# 4180_Board_rev1.net
KiCad netlist of a schematic drawn in EAGLE
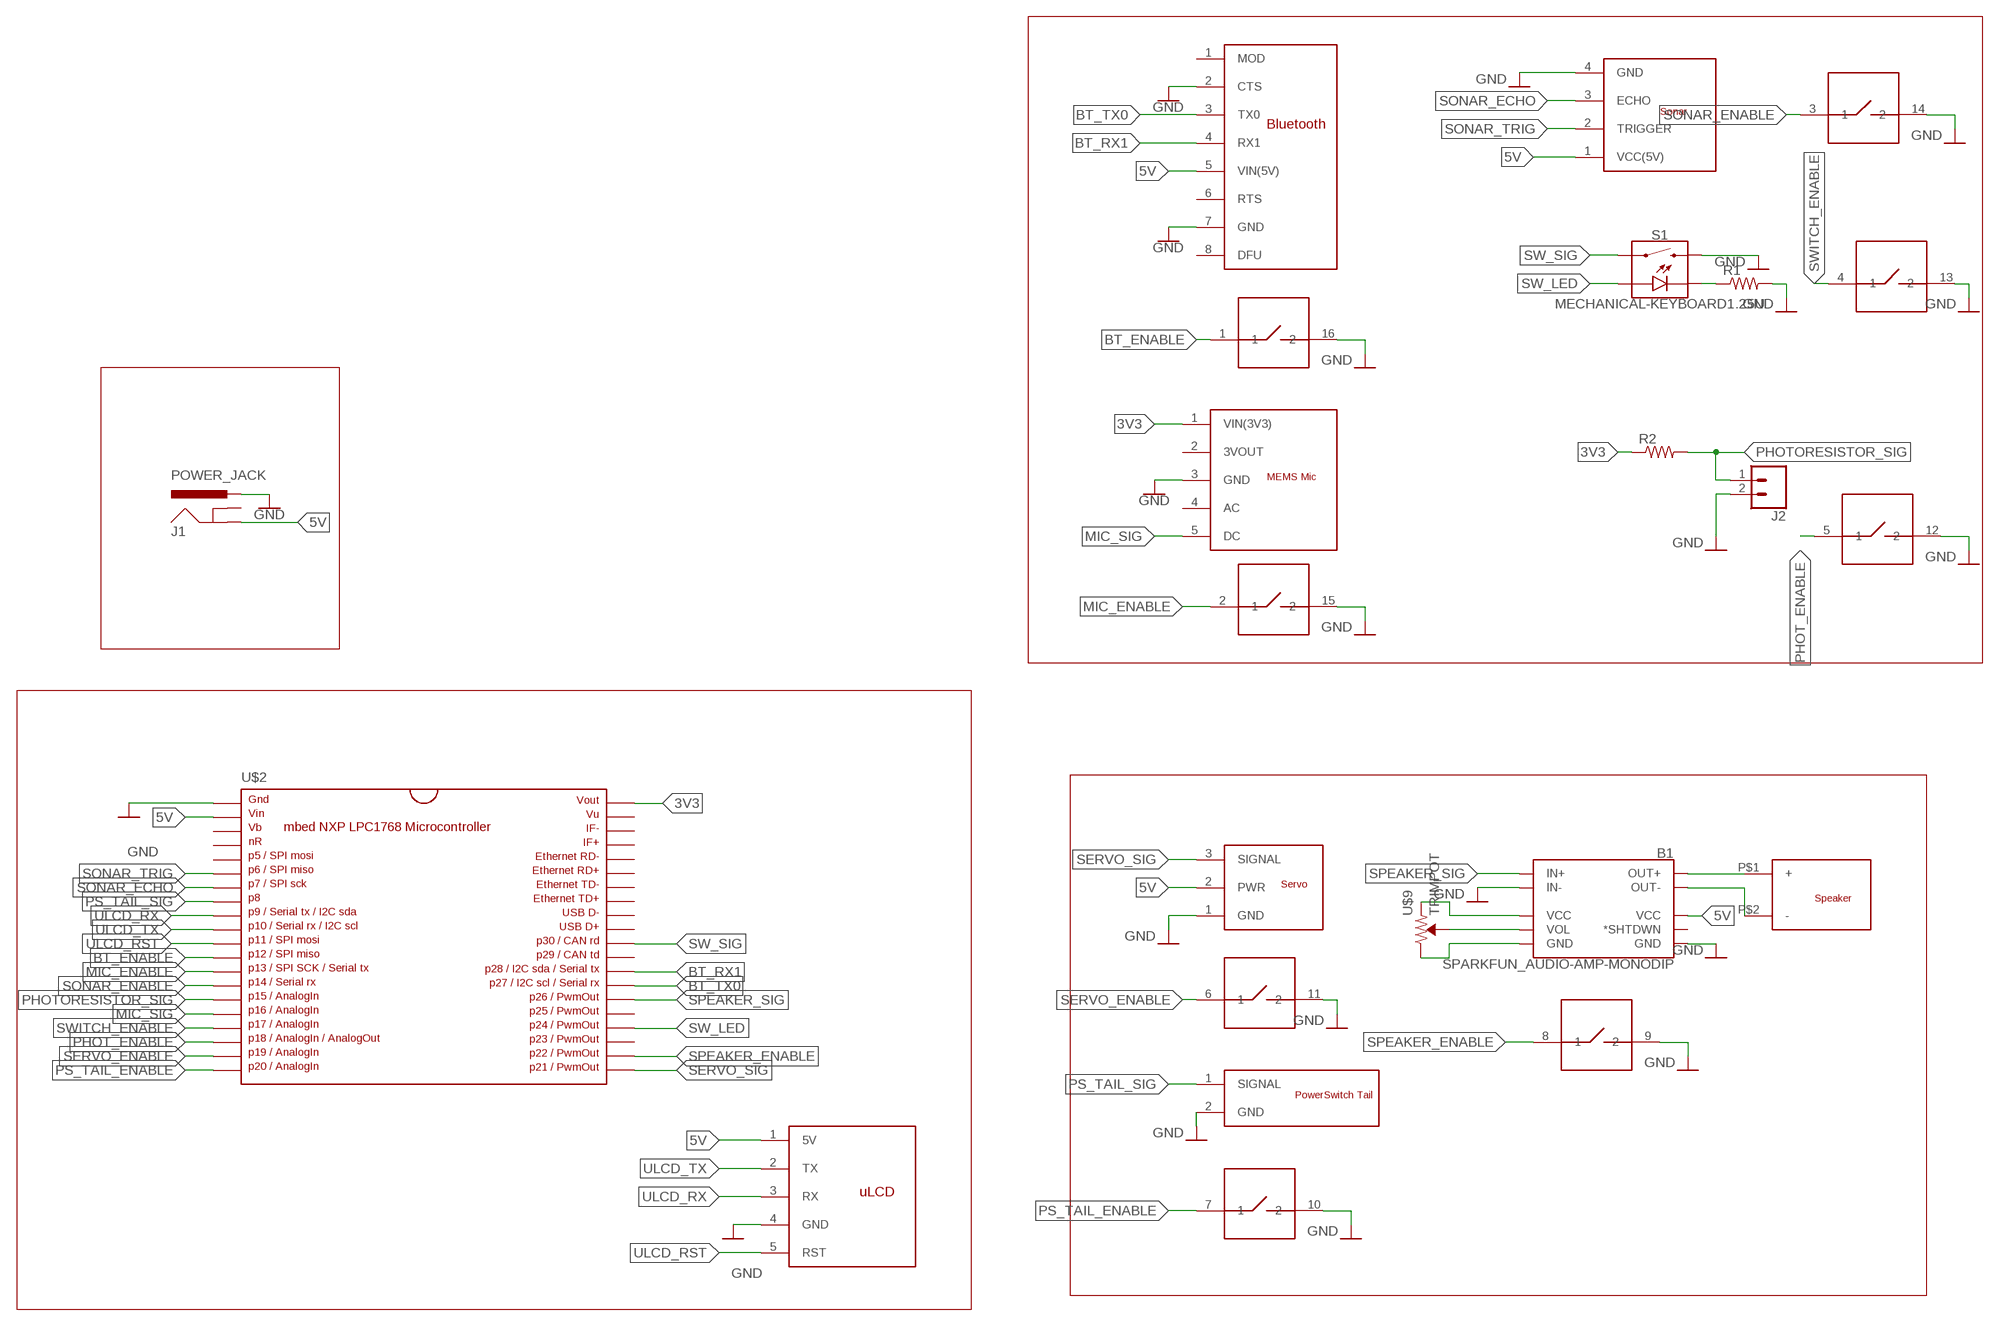
[diagram p0: schematic, sheet 1]

(export (version "E")
  (design (tool "Eeschema 10.0.6"))
  (components
    (comp (ref "B1")
      (value "SPARKFUN_AUDIO-AMP-MONODIP")
      (footprint "eagle-import:AUDIO-AMP-MONO")
      (libsource (lib "eagle-import") (part "SPARKFUN_AUDIO-AMP-MONODIP"))
    )
    (comp (ref "J1")
      (value "POWER_JACK")
      (footprint "eagle-import:POWER_JACK_PTH")
      (libsource (lib "eagle-import") (part "POWER_JACK"))
    )
    (comp (ref "J2")
      (value "CONN_02")
      (footprint "eagle-import:1X02")
      (libsource (lib "eagle-import") (part "CONN_02"))
    )
    (comp (ref "R1")
      (value "ADAFRUIT_R-US_0309/12")
      (footprint "eagle-import:ADAFRUIT_0309_12")
      (libsource (lib "eagle-import") (part "ADAFRUIT_R-US_0309/12"))
    )
    (comp (ref "R2")
      (value "ADAFRUIT_R-US_0309/12")
      (footprint "eagle-import:ADAFRUIT_0309_12")
      (libsource (lib "eagle-import") (part "ADAFRUIT_R-US_0309/12"))
    )
    (comp (ref "S1")
      (value "MECHANICAL-KEYBOARD1.25U")
      (footprint "eagle-import:CHERRY-MX-LED-1.25U")
      (libsource (lib "eagle-import") (part "MECHANICAL-KEYBOARD1.25U"))
    )
    (comp (ref "U$1")
      (value "BLUETOOTH")
      (footprint "eagle-import:1X08")
      (libsource (lib "eagle-import") (part "BLUETOOTH"))
    )
    (comp (ref "U$2")
      (value "MBED1768")
      (footprint "eagle-import:DIL40_0.9")
      (libsource (lib "eagle-import") (part "MBED_NXP_LPC1768"))
    )
    (comp (ref "U$3")
      (value "MEMS_MIC")
      (footprint "eagle-import:1X05")
      (libsource (lib "eagle-import") (part "MEMS_MIC"))
    )
    (comp (ref "U$4")
      (value "POWERSWITCHTAIL")
      (footprint "eagle-import:1X02")
      (libsource (lib "eagle-import") (part "POWERSWITCHTAIL"))
    )
    (comp (ref "U$5")
      (value "SERVO")
      (footprint "eagle-import:1X03")
      (libsource (lib "eagle-import") (part "SERVO"))
    )
    (comp (ref "U$6")
      (value "SONAR")
      (footprint "eagle-import:1X04")
      (libsource (lib "eagle-import") (part "SONAR"))
    )
    (comp (ref "U$7")
      (value "SPEAKER")
      (footprint "eagle-import:SPEAKER")
      (libsource (lib "eagle-import") (part "SPEAKER"))
    )
    (comp (ref "U$8")
      (value "ULCD")
      (footprint "eagle-import:1X05")
      (libsource (lib "eagle-import") (part "ULCD"))
    )
    (comp (ref "U$9")
      (value "TRIMPOT")
      (footprint "eagle-import:TRIMPOT")
      (libsource (lib "eagle-import") (part "TRIMPOT"))
    )
    (comp (ref "U$10")
      (value "DIP_SWITCH_8")
      (footprint "eagle-import:DIP16")
      (libsource (lib "eagle-import") (part "DIP_SWITCH_8"))
    )
  )
  (nets
    (net (code "1") (name "3V3") (class "Default")
      (node (ref "R2") (pin "1") (pinfunction "1_1") (pintype "passive"))
      (node (ref "U$2") (pin "40") (pinfunction "P$40_40") (pintype "bidirectional"))
      (node (ref "U$3") (pin "1") (pinfunction "VIN(3V3)_1") (pintype "bidirectional"))
    )
    (net (code "2") (name "5V") (class "Default")
      (node (ref "B1") (pin "PWR+") (pinfunction "VCC_PWR+") (pintype "bidirectional"))
      (node (ref "J1") (pin "PWR") (pinfunction "GND_PWR") (pintype "bidirectional"))
      (node (ref "U$1") (pin "5") (pinfunction "VIN(5V)_5") (pintype "bidirectional"))
      (node (ref "U$2") (pin "2") (pinfunction "P$2_2") (pintype "bidirectional"))
      (node (ref "U$5") (pin "2") (pinfunction "PWR_2") (pintype "bidirectional"))
      (node (ref "U$6") (pin "1") (pinfunction "VCC(5V)_1") (pintype "bidirectional"))
      (node (ref "U$8") (pin "1") (pinfunction "5V_1") (pintype "bidirectional"))
    )
    (net (code "3") (name "BT_ENABLE") (class "Default")
      (node (ref "U$10") (pin "1") (pinfunction "1_1") (pintype "bidirectional"))
      (node (ref "U$2") (pin "12") (pinfunction "P$12_12") (pintype "bidirectional"))
    )
    (net (code "4") (name "BT_RX1") (class "Default")
      (node (ref "U$1") (pin "4") (pinfunction "RX1_4") (pintype "bidirectional"))
      (node (ref "U$2") (pin "28") (pinfunction "P$28_28") (pintype "bidirectional"))
    )
    (net (code "5") (name "BT_TX0") (class "Default")
      (node (ref "U$1") (pin "3") (pinfunction "TX0_3") (pintype "bidirectional"))
      (node (ref "U$2") (pin "27") (pinfunction "P$27_27") (pintype "bidirectional"))
    )
    (net (code "6") (name "GND") (class "Default")
      (node (ref "B1") (pin "IN-") (pinfunction "IN-_IN-") (pintype "bidirectional"))
      (node (ref "B1") (pin "PWR-") (pinfunction "GND_PWR-") (pintype "bidirectional"))
      (node (ref "J1") (pin "GND") (pinfunction "PWR_GND") (pintype "bidirectional"))
      (node (ref "J2") (pin "2") (pinfunction "2_2") (pintype "passive"))
      (node (ref "R1") (pin "2") (pinfunction "2_2") (pintype "passive"))
      (node (ref "S1") (pin "S2") (pinfunction "2_S2") (pintype "passive"))
      (node (ref "U$1") (pin "2") (pinfunction "CTS_2") (pintype "bidirectional"))
      (node (ref "U$1") (pin "7") (pinfunction "GND_7") (pintype "bidirectional"))
      (node (ref "U$10") (pin "10") (pinfunction "2_10") (pintype "bidirectional"))
      (node (ref "U$10") (pin "11") (pinfunction "2_11") (pintype "bidirectional"))
      (node (ref "U$10") (pin "12") (pinfunction "2_12") (pintype "bidirectional"))
      (node (ref "U$10") (pin "13") (pinfunction "2_13") (pintype "bidirectional"))
      (node (ref "U$10") (pin "14") (pinfunction "2_14") (pintype "bidirectional"))
      (node (ref "U$10") (pin "15") (pinfunction "2_15") (pintype "bidirectional"))
      (node (ref "U$10") (pin "16") (pinfunction "2_16") (pintype "bidirectional"))
      (node (ref "U$10") (pin "9") (pinfunction "2_9") (pintype "bidirectional"))
      (node (ref "U$2") (pin "1") (pinfunction "P$1_1") (pintype "bidirectional"))
      (node (ref "U$3") (pin "3") (pinfunction "GND_3") (pintype "bidirectional"))
      (node (ref "U$4") (pin "2") (pinfunction "GND_2") (pintype "bidirectional"))
      (node (ref "U$5") (pin "1") (pinfunction "GND_1") (pintype "bidirectional"))
      (node (ref "U$6") (pin "4") (pinfunction "GND_4") (pintype "bidirectional"))
      (node (ref "U$8") (pin "4") (pinfunction "GND_4") (pintype "bidirectional"))
    )
    (net (code "7") (name "MIC_ENABLE") (class "Default")
      (node (ref "U$10") (pin "2") (pinfunction "1_2") (pintype "bidirectional"))
      (node (ref "U$2") (pin "13") (pinfunction "P$13_13") (pintype "bidirectional"))
    )
    (net (code "8") (name "MIC_SIG") (class "Default")
      (node (ref "U$2") (pin "16") (pinfunction "P$16_16") (pintype "bidirectional"))
      (node (ref "U$3") (pin "5") (pinfunction "DC_5") (pintype "bidirectional"))
    )
    (net (code "9") (name "Net-(S1-C)") (class "Default")
      (node (ref "R1") (pin "1") (pinfunction "1_1") (pintype "passive"))
      (node (ref "S1") (pin "K") (pinfunction "C_K") (pintype "passive"))
    )
    (net (code "10") (name "Net-(U$7-+)") (class "Default")
      (node (ref "B1") (pin "OUT+") (pinfunction "OUT+_OUT+") (pintype "bidirectional"))
      (node (ref "U$7") (pin "P$1") (pinfunction "+_P$1") (pintype "bidirectional"))
    )
    (net (code "11") (name "Net-(U$7--)") (class "Default")
      (node (ref "B1") (pin "OUT-") (pinfunction "OUT-_OUT-") (pintype "bidirectional"))
      (node (ref "U$7") (pin "P$2") (pinfunction "-_P$2") (pintype "bidirectional"))
    )
    (net (code "12") (name "Net-(U$9-CCW)") (class "Default")
      (node (ref "B1") (pin "VOL+") (pinfunction "VCC_VOL+") (pintype "bidirectional"))
      (node (ref "U$9") (pin "P$1") (pinfunction "CCW_P$1") (pintype "passive"))
    )
    (net (code "13") (name "Net-(U$9-CW)") (class "Default")
      (node (ref "B1") (pin "VOL-") (pinfunction "GND_VOL-") (pintype "bidirectional"))
      (node (ref "U$9") (pin "P$2") (pinfunction "CW_P$2") (pintype "passive"))
    )
    (net (code "14") (name "Net-(U$9-WIPER)") (class "Default")
      (node (ref "B1") (pin "VOL") (pinfunction "VOL_VOL") (pintype "bidirectional"))
      (node (ref "U$9") (pin "P$3") (pinfunction "WIPER_P$3") (pintype "passive"))
    )
    (net (code "15") (name "PHOTORESISTOR_SIG") (class "Default")
      (node (ref "J2") (pin "1") (pinfunction "1_1") (pintype "passive"))
      (node (ref "R2") (pin "2") (pinfunction "2_2") (pintype "passive"))
      (node (ref "U$2") (pin "15") (pinfunction "P$15_15") (pintype "bidirectional"))
    )
    (net (code "16") (name "PHOT_ENABLE") (class "Default")
      (node (ref "U$10") (pin "5") (pinfunction "1_5") (pintype "bidirectional"))
      (node (ref "U$2") (pin "18") (pinfunction "P$18_18") (pintype "bidirectional"))
    )
    (net (code "17") (name "PS_TAIL_ENABLE") (class "Default")
      (node (ref "U$10") (pin "7") (pinfunction "1_7") (pintype "bidirectional"))
      (node (ref "U$2") (pin "20") (pinfunction "P$20_20") (pintype "bidirectional"))
    )
    (net (code "18") (name "PS_TAIL_SIG") (class "Default")
      (node (ref "U$2") (pin "8") (pinfunction "P$8_8") (pintype "bidirectional"))
      (node (ref "U$4") (pin "1") (pinfunction "SIGNAL_1") (pintype "bidirectional"))
    )
    (net (code "19") (name "SERVO_ENABLE") (class "Default")
      (node (ref "U$10") (pin "6") (pinfunction "1_6") (pintype "bidirectional"))
      (node (ref "U$2") (pin "19") (pinfunction "P$19_19") (pintype "bidirectional"))
    )
    (net (code "20") (name "SERVO_SIG") (class "Default")
      (node (ref "U$2") (pin "21") (pinfunction "P$21_21") (pintype "bidirectional"))
      (node (ref "U$5") (pin "3") (pinfunction "SIGNAL_3") (pintype "bidirectional"))
    )
    (net (code "21") (name "SONAR_ECHO") (class "Default")
      (node (ref "U$2") (pin "7") (pinfunction "P$7_7") (pintype "bidirectional"))
      (node (ref "U$6") (pin "3") (pinfunction "ECHO_3") (pintype "bidirectional"))
    )
    (net (code "22") (name "SONAR_ENABLE") (class "Default")
      (node (ref "U$10") (pin "3") (pinfunction "1_3") (pintype "bidirectional"))
      (node (ref "U$2") (pin "14") (pinfunction "P$14_14") (pintype "bidirectional"))
    )
    (net (code "23") (name "SONAR_TRIG") (class "Default")
      (node (ref "U$2") (pin "6") (pinfunction "P$6_6") (pintype "bidirectional"))
      (node (ref "U$6") (pin "2") (pinfunction "TRIGGER_2") (pintype "bidirectional"))
    )
    (net (code "24") (name "SPEAKER_ENABLE") (class "Default")
      (node (ref "U$10") (pin "8") (pinfunction "1_8") (pintype "bidirectional"))
      (node (ref "U$2") (pin "22") (pinfunction "P$22_22") (pintype "bidirectional"))
    )
    (net (code "25") (name "SPEAKER_SIG") (class "Default")
      (node (ref "B1") (pin "IN+") (pinfunction "IN+_IN+") (pintype "bidirectional"))
      (node (ref "U$2") (pin "26") (pinfunction "P$26_26") (pintype "bidirectional"))
    )
    (net (code "26") (name "SWITCH_ENABLE") (class "Default")
      (node (ref "U$10") (pin "4") (pinfunction "1_4") (pintype "bidirectional"))
      (node (ref "U$2") (pin "17") (pinfunction "P$17_17") (pintype "bidirectional"))
    )
    (net (code "27") (name "SW_LED") (class "Default")
      (node (ref "S1") (pin "A") (pinfunction "A_A") (pintype "passive"))
      (node (ref "U$2") (pin "24") (pinfunction "P$24_24") (pintype "bidirectional"))
    )
    (net (code "28") (name "SW_SIG") (class "Default")
      (node (ref "S1") (pin "S1") (pinfunction "1_S1") (pintype "passive"))
      (node (ref "U$2") (pin "30") (pinfunction "P$30_30") (pintype "bidirectional"))
    )
    (net (code "29") (name "ULCD_RST") (class "Default")
      (node (ref "U$2") (pin "11") (pinfunction "P$11_11") (pintype "bidirectional"))
      (node (ref "U$8") (pin "5") (pinfunction "RST_5") (pintype "bidirectional"))
    )
    (net (code "30") (name "ULCD_RX") (class "Default")
      (node (ref "U$2") (pin "9") (pinfunction "P$9_9") (pintype "bidirectional"))
      (node (ref "U$8") (pin "3") (pinfunction "RX_3") (pintype "bidirectional"))
    )
    (net (code "31") (name "ULCD_TX") (class "Default")
      (node (ref "U$2") (pin "10") (pinfunction "P$10_10") (pintype "bidirectional"))
      (node (ref "U$8") (pin "2") (pinfunction "TX_2") (pintype "bidirectional"))
    )
    (net (code "32") (name "unconnected-(B1-*SHTDWN-PadS)") (class "Default")
      (node (ref "B1") (pin "S") (pinfunction "*SHTDWN_S") (pintype "bidirectional"))
    )
    (net (code "33") (name "unconnected-(J1-PadGNDBREAK)") (class "Default")
      (node (ref "J1") (pin "GNDBREAK") (pinfunction "GNDBREAK_GNDBREAK") (pintype "bidirectional"))
    )
    (net (code "34") (name "unconnected-(U$1-DFU-Pad8)") (class "Default")
      (node (ref "U$1") (pin "8") (pinfunction "DFU_8") (pintype "bidirectional"))
    )
    (net (code "35") (name "unconnected-(U$1-MOD-Pad1)") (class "Default")
      (node (ref "U$1") (pin "1") (pinfunction "MOD_1") (pintype "bidirectional"))
    )
    (net (code "36") (name "unconnected-(U$1-RTS-Pad6)") (class "Default")
      (node (ref "U$1") (pin "6") (pinfunction "RTS_6") (pintype "bidirectional"))
    )
    (net (code "37") (name "unconnected-(U$2-P$3-Pad3)") (class "Default")
      (node (ref "U$2") (pin "3") (pinfunction "P$3_3") (pintype "bidirectional"))
    )
    (net (code "38") (name "unconnected-(U$2-P$4-Pad4)") (class "Default")
      (node (ref "U$2") (pin "4") (pinfunction "P$4_4") (pintype "bidirectional"))
    )
    (net (code "39") (name "unconnected-(U$2-P$5-Pad5)") (class "Default")
      (node (ref "U$2") (pin "5") (pinfunction "P$5_5") (pintype "bidirectional"))
    )
    (net (code "40") (name "unconnected-(U$2-P$23-Pad23)") (class "Default")
      (node (ref "U$2") (pin "23") (pinfunction "P$23_23") (pintype "bidirectional"))
    )
    (net (code "41") (name "unconnected-(U$2-P$25-Pad25)") (class "Default")
      (node (ref "U$2") (pin "25") (pinfunction "P$25_25") (pintype "bidirectional"))
    )
    (net (code "42") (name "unconnected-(U$2-P$29-Pad29)") (class "Default")
      (node (ref "U$2") (pin "29") (pinfunction "P$29_29") (pintype "bidirectional"))
    )
    (net (code "43") (name "unconnected-(U$2-P$31-Pad31)") (class "Default")
      (node (ref "U$2") (pin "31") (pinfunction "P$31_31") (pintype "bidirectional"))
    )
    (net (code "44") (name "unconnected-(U$2-P$32-Pad32)") (class "Default")
      (node (ref "U$2") (pin "32") (pinfunction "P$32_32") (pintype "bidirectional"))
    )
    (net (code "45") (name "unconnected-(U$2-P$33-Pad33)") (class "Default")
      (node (ref "U$2") (pin "33") (pinfunction "P$33_33") (pintype "bidirectional"))
    )
    (net (code "46") (name "unconnected-(U$2-P$34-Pad34)") (class "Default")
      (node (ref "U$2") (pin "34") (pinfunction "P$34_34") (pintype "bidirectional"))
    )
    (net (code "47") (name "unconnected-(U$2-P$35-Pad35)") (class "Default")
      (node (ref "U$2") (pin "35") (pinfunction "P$35_35") (pintype "bidirectional"))
    )
    (net (code "48") (name "unconnected-(U$2-P$36-Pad36)") (class "Default")
      (node (ref "U$2") (pin "36") (pinfunction "P$36_36") (pintype "bidirectional"))
    )
    (net (code "49") (name "unconnected-(U$2-P$37-Pad37)") (class "Default")
      (node (ref "U$2") (pin "37") (pinfunction "P$37_37") (pintype "bidirectional"))
    )
    (net (code "50") (name "unconnected-(U$2-P$38-Pad38)") (class "Default")
      (node (ref "U$2") (pin "38") (pinfunction "P$38_38") (pintype "bidirectional"))
    )
    (net (code "51") (name "unconnected-(U$2-P$39-Pad39)") (class "Default")
      (node (ref "U$2") (pin "39") (pinfunction "P$39_39") (pintype "bidirectional"))
    )
    (net (code "52") (name "unconnected-(U$3-3VOUT-Pad2)") (class "Default")
      (node (ref "U$3") (pin "2") (pinfunction "3VOUT_2") (pintype "bidirectional"))
    )
    (net (code "53") (name "unconnected-(U$3-AC-Pad4)") (class "Default")
      (node (ref "U$3") (pin "4") (pinfunction "AC_4") (pintype "bidirectional"))
    )
  )
)
